# Himax.net
KiCad netlist of a schematic drawn in Altium Designer
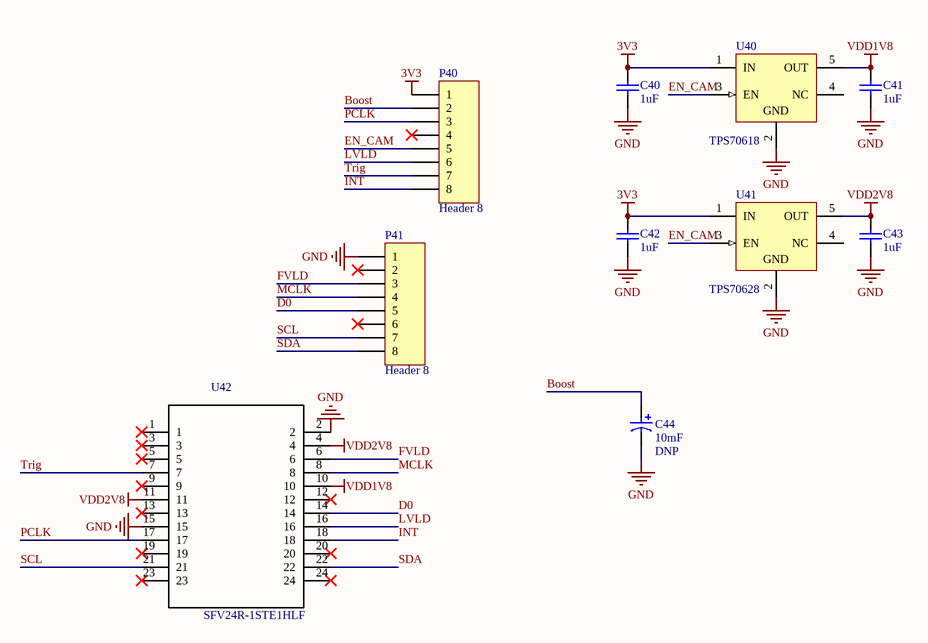
[diagram p0: Himax.SchDoc]

(export (version "E")
  (design (tool "Eeschema 10.0.6"))
  (components
    (comp (ref "C40")
      (value "1uF")
      (footprint "0402")
      (description "CAP CER 1UF 10V X5R 0402")
      (fields
        (field (name "DIGI-KEY PART NUMBER") "1276-1076-1-ND")
        (field (name "MANUFACTURER") "Samsung Electro-Mechanics")
      )
      (libsource (lib "WISP6") (part "C-1uF-10V-X5R-0402"))
    )
    (comp (ref "C41")
      (value "1uF")
      (footprint "0402")
      (description "CAP CER 1UF 10V X5R 0402")
      (fields
        (field (name "DIGI-KEY PART NUMBER") "1276-1076-1-ND")
        (field (name "MANUFACTURER") "Samsung Electro-Mechanics")
      )
      (libsource (lib "WISP6") (part "C-1uF-10V-X5R-0402"))
    )
    (comp (ref "C42")
      (value "1uF")
      (footprint "0402")
      (description "CAP CER 1UF 10V X5R 0402")
      (fields
        (field (name "DIGI-KEY PART NUMBER") "1276-1076-1-ND")
        (field (name "MANUFACTURER") "Samsung Electro-Mechanics")
      )
      (libsource (lib "WISP6") (part "C-1uF-10V-X5R-0402"))
    )
    (comp (ref "C43")
      (value "1uF")
      (footprint "0402")
      (description "CAP CER 1UF 10V X5R 0402")
      (fields
        (field (name "DIGI-KEY PART NUMBER") "1276-1076-1-ND")
        (field (name "MANUFACTURER") "Samsung Electro-Mechanics")
      )
      (libsource (lib "WISP6") (part "C-1uF-10V-X5R-0402"))
    )
    (comp (ref "C44")
      (value "DNP")
      (footprint "CAPPRD500W60D1000H3200")
      (description "Electrolytic capacitor")
      (fields (field (name "NOTE") "10mF") (field (name "Comment") "Generic electrolytic capacitor"))
      (libsource (lib "WISP6") (part "cap_electrolytic"))
    )
    (comp (ref "P40")
      (value "Header 8")
      (footprint "HDR1X8")
      (description "Header, 8-Pin")
      (fields (field (name "PUBLISHER") "Altium Limited"))
      (libsource (lib "Miscellaneous Connectors") (part "Header 8"))
    )
    (comp (ref "P41")
      (value "Header 8")
      (footprint "HDR1X8")
      (description "Header, 8-Pin")
      (fields (field (name "PUBLISHER") "Altium Limited"))
      (libsource (lib "Miscellaneous Connectors") (part "Header 8"))
    )
    (comp (ref "U40")
      (value "TPS70618")
      (footprint "TI-DDC5_M")
      (description "Linear Voltage Regulator IC Positive Fixed 1 Output 150mA SOT-23-5")
      (fields
        (field (name "MANUFACTURER") "Texas Instruments")
        (field (name "MANUFACTURER PART NUMBER") "TPS70618DBVR")
      )
      (libsource (lib "BLE") (part "TPS706xx"))
    )
    (comp (ref "U41")
      (value "TPS70628")
      (footprint "TI-DDC5_M")
      (description "Linear Voltage Regulator IC Positive Fixed 1 Output 150mA SOT-23-5")
      (fields
        (field (name "MANUFACTURER") "Texas Instruments")
        (field (name "MANUFACTURER PART NUMBER") "TPS70628DBVR")
      )
      (libsource (lib "BLE") (part "TPS706xx"))
    )
    (comp (ref "U42")
      (value "SFV24R-1STE1HLF")
      (footprint "FCI_SFV24R-2STE1LF")
      (description "Himax Camera Connector")
      (fields (field (name "MANUFACTURER") "Amphenol FCI"))
      (libsource (lib "BLE") (part "SFV24R-1STE1HLF"))
    )
  )
  (nets
    (net (code "1") (name "/Boost") (class "Default")
      (node (ref "C44") (pin "P") (pinfunction "P_P") (pintype "passive"))
      (node (ref "P40") (pin "2") (pinfunction "2_2") (pintype "passive"))
    )
    (net (code "2") (name "/D0") (class "Default")
      (node (ref "P41") (pin "5") (pinfunction "5_5") (pintype "passive"))
      (node (ref "U42") (pin "14") (pinfunction "14_14") (pintype "passive"))
    )
    (net (code "3") (name "/EN_CAM") (class "Default")
      (node (ref "P40") (pin "5") (pinfunction "5_5") (pintype "passive"))
      (node (ref "U40") (pin "3") (pinfunction "EN_3") (pintype "input"))
      (node (ref "U41") (pin "3") (pinfunction "EN_3") (pintype "input"))
    )
    (net (code "4") (name "/FVLD") (class "Default")
      (node (ref "P41") (pin "3") (pinfunction "3_3") (pintype "passive"))
      (node (ref "U42") (pin "6") (pinfunction "6_6") (pintype "passive"))
    )
    (net (code "5") (name "/INT") (class "Default")
      (node (ref "P40") (pin "8") (pinfunction "8_8") (pintype "passive"))
      (node (ref "U42") (pin "18") (pinfunction "18_18") (pintype "passive"))
    )
    (net (code "6") (name "/LVLD") (class "Default")
      (node (ref "P40") (pin "6") (pinfunction "6_6") (pintype "passive"))
      (node (ref "U42") (pin "16") (pinfunction "16_16") (pintype "passive"))
    )
    (net (code "7") (name "/MCLK") (class "Default")
      (node (ref "P41") (pin "4") (pinfunction "4_4") (pintype "passive"))
      (node (ref "U42") (pin "8") (pinfunction "8_8") (pintype "passive"))
    )
    (net (code "8") (name "/PCLK") (class "Default")
      (node (ref "P40") (pin "3") (pinfunction "3_3") (pintype "passive"))
      (node (ref "U42") (pin "17") (pinfunction "17_17") (pintype "passive"))
    )
    (net (code "9") (name "/SCL") (class "Default")
      (node (ref "P41") (pin "7") (pinfunction "7_7") (pintype "passive"))
      (node (ref "U42") (pin "21") (pinfunction "21_21") (pintype "passive"))
    )
    (net (code "10") (name "/SDA") (class "Default")
      (node (ref "P41") (pin "8") (pinfunction "8_8") (pintype "passive"))
      (node (ref "U42") (pin "22") (pinfunction "22_22") (pintype "passive"))
    )
    (net (code "11") (name "/Trig") (class "Default")
      (node (ref "P40") (pin "7") (pinfunction "7_7") (pintype "passive"))
      (node (ref "U42") (pin "7") (pinfunction "7_7") (pintype "passive"))
    )
    (net (code "12") (name "3V3") (class "Default")
      (node (ref "C40") (pin "2") (pinfunction "2_2") (pintype "passive"))
      (node (ref "C42") (pin "2") (pinfunction "2_2") (pintype "passive"))
      (node (ref "P40") (pin "1") (pinfunction "1_1") (pintype "passive"))
      (node (ref "U40") (pin "1") (pinfunction "IN_1") (pintype "power_in"))
      (node (ref "U41") (pin "1") (pinfunction "IN_1") (pintype "power_in"))
    )
    (net (code "13") (name "GND") (class "Default")
      (node (ref "C40") (pin "1") (pinfunction "1_1") (pintype "passive"))
      (node (ref "C41") (pin "1") (pinfunction "1_1") (pintype "passive"))
      (node (ref "C42") (pin "1") (pinfunction "1_1") (pintype "passive"))
      (node (ref "C43") (pin "1") (pinfunction "1_1") (pintype "passive"))
      (node (ref "C44") (pin "N") (pinfunction "N_N") (pintype "passive"))
      (node (ref "P41") (pin "1") (pinfunction "1_1") (pintype "passive"))
      (node (ref "U40") (pin "2") (pinfunction "GND_2") (pintype "power_in"))
      (node (ref "U41") (pin "2") (pinfunction "GND_2") (pintype "power_in"))
      (node (ref "U42") (pin "15") (pinfunction "15_15") (pintype "passive"))
      (node (ref "U42") (pin "2") (pinfunction "2_2") (pintype "passive"))
    )
    (net (code "14") (name "VDD1V8") (class "Default")
      (node (ref "C41") (pin "2") (pinfunction "2_2") (pintype "passive"))
      (node (ref "U40") (pin "5") (pinfunction "OUT_5") (pintype "power_in"))
      (node (ref "U42") (pin "10") (pinfunction "10_10") (pintype "passive"))
    )
    (net (code "15") (name "VDD2V8") (class "Default")
      (node (ref "C43") (pin "2") (pinfunction "2_2") (pintype "passive"))
      (node (ref "U41") (pin "5") (pinfunction "OUT_5") (pintype "power_in"))
      (node (ref "U42") (pin "11") (pinfunction "11_11") (pintype "passive"))
      (node (ref "U42") (pin "4") (pinfunction "4_4") (pintype "passive"))
    )
    (net (code "16") (name "unconnected-(P40-Pad4)") (class "Default")
      (node (ref "P40") (pin "4") (pinfunction "4_4") (pintype "passive+no_connect"))
    )
    (net (code "17") (name "unconnected-(P41-Pad2)") (class "Default")
      (node (ref "P41") (pin "2") (pinfunction "2_2") (pintype "passive+no_connect"))
    )
    (net (code "18") (name "unconnected-(P41-Pad6)") (class "Default")
      (node (ref "P41") (pin "6") (pinfunction "6_6") (pintype "passive+no_connect"))
    )
    (net (code "19") (name "unconnected-(U40-NC-Pad4)") (class "Default")
      (node (ref "U40") (pin "4") (pinfunction "NC_4") (pintype "passive"))
    )
    (net (code "20") (name "unconnected-(U41-NC-Pad4)") (class "Default")
      (node (ref "U41") (pin "4") (pinfunction "NC_4") (pintype "passive"))
    )
    (net (code "21") (name "unconnected-(U42-Pad1)") (class "Default")
      (node (ref "U42") (pin "1") (pinfunction "1_1") (pintype "passive+no_connect"))
    )
    (net (code "22") (name "unconnected-(U42-Pad3)") (class "Default")
      (node (ref "U42") (pin "3") (pinfunction "3_3") (pintype "passive+no_connect"))
    )
    (net (code "23") (name "unconnected-(U42-Pad5)") (class "Default")
      (node (ref "U42") (pin "5") (pinfunction "5_5") (pintype "passive+no_connect"))
    )
    (net (code "24") (name "unconnected-(U42-Pad9)") (class "Default")
      (node (ref "U42") (pin "9") (pinfunction "9_9") (pintype "passive+no_connect"))
    )
    (net (code "25") (name "unconnected-(U42-Pad12)") (class "Default")
      (node (ref "U42") (pin "12") (pinfunction "12_12") (pintype "passive+no_connect"))
    )
    (net (code "26") (name "unconnected-(U42-Pad13)") (class "Default")
      (node (ref "U42") (pin "13") (pinfunction "13_13") (pintype "passive+no_connect"))
    )
    (net (code "27") (name "unconnected-(U42-Pad19)") (class "Default")
      (node (ref "U42") (pin "19") (pinfunction "19_19") (pintype "passive+no_connect"))
    )
    (net (code "28") (name "unconnected-(U42-Pad20)") (class "Default")
      (node (ref "U42") (pin "20") (pinfunction "20_20") (pintype "passive+no_connect"))
    )
    (net (code "29") (name "unconnected-(U42-Pad23)") (class "Default")
      (node (ref "U42") (pin "23") (pinfunction "23_23") (pintype "passive+no_connect"))
    )
    (net (code "30") (name "unconnected-(U42-Pad24)") (class "Default")
      (node (ref "U42") (pin "24") (pinfunction "24_24") (pintype "passive+no_connect"))
    )
  )
)
